# Ancillaries.net
KiCad netlist of a schematic drawn in Altium Designer
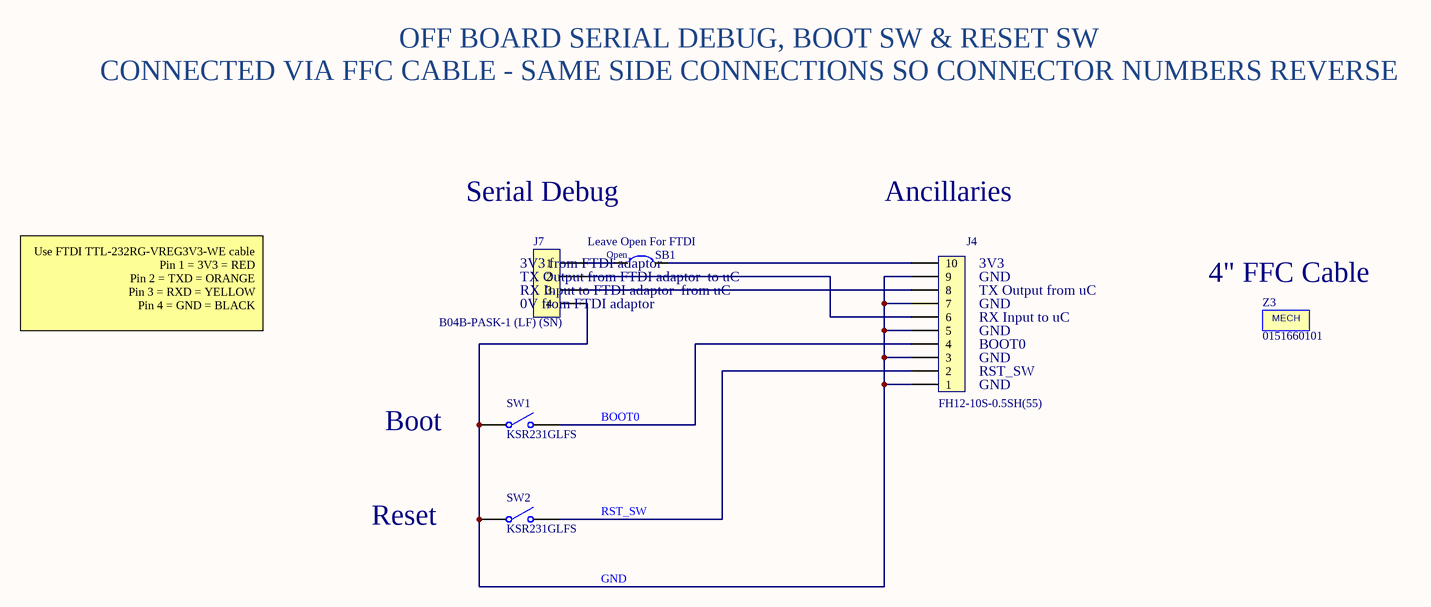
[diagram p0: Ancillaries.SchDoc]

(export (version "E")
  (design (tool "Eeschema 10.0.6"))
  (components
    (comp (ref "J4")
      (value "Ancillaries")
      (footprint "FH12-10S-0_5SH")
      (description "Connector 10W FFC/FPC 0.5mm SM ZIF")
      (fields (field (name "MANUPARTNO") "FH12-10S-0.5SH(55)") (field (name "MANUFACTURER") "Hirose"))
      (libsource (lib "Library") (part "CON10"))
    )
    (comp (ref "J7")
      (value "Serial Debug")
      (footprint "B04B-PASK-1")
      (description "Connector 4 Way Vertical JST B04B-PASK-1 (LF) (SN) 2mm Pitch")
      (fields (field (name "MANUPARTNO") "B04B-PASK-1 (LF) (SN)") (field (name "MANUFACTURER") "JST"))
      (libsource (lib "Library") (part "CON4"))
    )
    (comp (ref "SB1")
      (value "Leave Open For FTDI")
      (footprint "0603SolderLinkOpen")
      (description "Solder Blob - Open 0603 SM pads")
      (libsource (lib "Library") (part "Solder Blob Open"))
    )
    (comp (ref "SW1")
      (value "Boot")
      (footprint "SW_KSR")
      (description "Switch SMD SPST-NO Vertical ITT/Cannon KSR231GLFS")
      (fields (field (name "MANUPARTNO") "KSR231GLFS") (field (name "MANUFACTURER") "ITT/Cannon"))
      (libsource (lib "Library") (part "SPST"))
    )
    (comp (ref "SW2")
      (value "Reset")
      (footprint "SW_KSR")
      (description "Switch SMD SPST-NO Vertical ITT/Cannon KSR231GLFS")
      (fields (field (name "MANUPARTNO") "KSR231GLFS") (field (name "MANUFACTURER") "ITT/Cannon"))
      (libsource (lib "Library") (part "SPST"))
    )
    (comp (ref "Z3")
      (value "4\" FFC Cable")
      (description "CABLE FFC/FPC 10POS 0.5MM 4\"")
      (fields (field (name "MANUPARTNO") "0151660101") (field (name "MANUFACTURER") "Molex"))
      (libsource (lib "Library") (part "MECH"))
    )
  )
  (nets
    (net (code "1") (name "Net-(J4-Pad6)") (class "Default")
      (node (ref "J4") (pin "6") (pinfunction "6_6") (pintype "passive"))
      (node (ref "J7") (pin "2") (pinfunction "2_2") (pintype "passive"))
    )
    (net (code "2") (name "Net-(J4-Pad8)") (class "Default")
      (node (ref "J4") (pin "8") (pinfunction "8_8") (pintype "passive"))
      (node (ref "J7") (pin "3") (pinfunction "3_3") (pintype "passive"))
    )
    (net (code "3") (name "Net-(J4-Pad10)") (class "Default")
      (node (ref "J4") (pin "10") (pinfunction "10_10") (pintype "passive"))
      (node (ref "SB1") (pin "2") (pinfunction "2_2") (pintype "passive"))
    )
    (net (code "4") (name "Net-(J7-Pad1)") (class "Default")
      (node (ref "J7") (pin "1") (pinfunction "1_1") (pintype "passive"))
      (node (ref "SB1") (pin "1") (pinfunction "1_1") (pintype "passive"))
    )
    (net (code "5") (name "Net-(SW1-COMMON)") (class "Default")
      (node (ref "J4") (pin "1") (pinfunction "1_1") (pintype "passive"))
      (node (ref "J4") (pin "3") (pinfunction "3_3") (pintype "passive"))
      (node (ref "J4") (pin "5") (pinfunction "5_5") (pintype "passive"))
      (node (ref "J4") (pin "7") (pinfunction "7_7") (pintype "passive"))
      (node (ref "J4") (pin "9") (pinfunction "9_9") (pintype "passive"))
      (node (ref "J7") (pin "4") (pinfunction "4_4") (pintype "passive"))
      (node (ref "SW1") (pin "1") (pinfunction "COMMON_1") (pintype "passive"))
      (node (ref "SW2") (pin "1") (pinfunction "COMMON_1") (pintype "passive"))
    )
    (net (code "6") (name "Net-(SW1-NO)") (class "Default")
      (node (ref "J4") (pin "4") (pinfunction "4_4") (pintype "passive"))
      (node (ref "SW1") (pin "2") (pinfunction "NO_2") (pintype "passive"))
    )
    (net (code "7") (name "Net-(SW2-NO)") (class "Default")
      (node (ref "J4") (pin "2") (pinfunction "2_2") (pintype "passive"))
      (node (ref "SW2") (pin "2") (pinfunction "NO_2") (pintype "passive"))
    )
  )
)
